# Placa3.net
KiCad netlist of a schematic drawn in Altium Designer
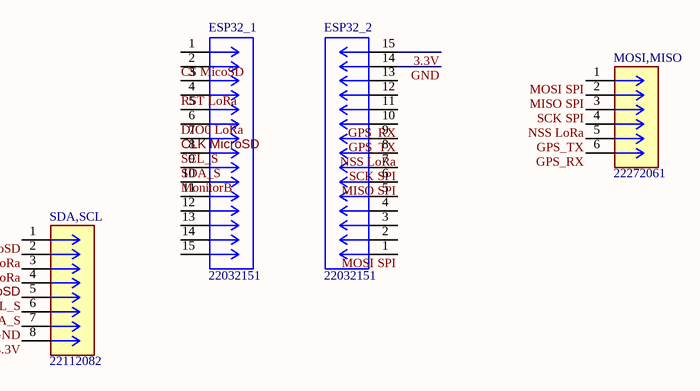
[diagram p0: Placa3.SchDoc]

(export (version "E")
  (design (tool "Eeschema 10.0.6"))
  (components
    (comp (ref "ESP32_1")
      (value "22032151")
      (footprint "CONN15X1_22032151_MOL")
      (description "Conn Unshrouded Header HDR 15 POS 2.54mm Solder ST Thru-Hole KKÂ® Bag")
      (fields (field (name "MF") "Molex"))
      (libsource (lib "22032151") (part "22032151"))
    )
    (comp (ref "ESP32_2")
      (value "22032151")
      (footprint "CONN15X1_22032151_MOL")
      (description "Conn Unshrouded Header HDR 15 POS 2.54mm Solder ST Thru-Hole KKÂ® Bag")
      (fields (field (name "MF") "Molex"))
      (libsource (lib "22032151") (part "22032151"))
    )
    (comp (ref "MOSI,MISO")
      (value "22272061")
      (footprint "CONN_AE-6410-06A_MOL")
      (libsource (lib "22272061") (part "22272061"))
    )
    (comp (ref "SDA,SCL")
      (value "22112082")
      (footprint "CONN_A-6373-08A_MOL")
      (description "KKÂ® 254 Solid Header, Vertical, with Friction Lock, 8 Circuits, Gold (Au) Plating")
      (fields (field (name "MF") "Molex") (field (name "MP") "22-11-2082"))
      (libsource (lib "22112082") (part "22112082"))
    )
  )
  (nets
    (net (code "1") (name "/3.3V") (class "Default")
      (node (ref "ESP32_2") (pin "15") (pinfunction "15_15") (pintype "passive"))
      (node (ref "SDA,SCL") (pin "8") (pinfunction "8_8") (pintype "passive"))
    )
    (net (code "2") (name "/CLK MicroSD") (class "Default")
      (node (ref "ESP32_1") (pin "8") (pinfunction "8_8") (pintype "passive"))
      (node (ref "SDA,SCL") (pin "4") (pinfunction "4_4") (pintype "passive"))
    )
    (net (code "3") (name "/CS MicoSD") (class "Default")
      (node (ref "ESP32_1") (pin "3") (pinfunction "3_3") (pintype "passive"))
      (node (ref "SDA,SCL") (pin "1") (pinfunction "1_1") (pintype "passive"))
    )
    (net (code "4") (name "/DIO0 LoRa") (class "Default")
      (node (ref "ESP32_1") (pin "7") (pinfunction "7_7") (pintype "passive"))
      (node (ref "SDA,SCL") (pin "3") (pinfunction "3_3") (pintype "passive"))
    )
    (net (code "5") (name "/GND") (class "Default")
      (node (ref "ESP32_2") (pin "14") (pinfunction "14_14") (pintype "passive"))
      (node (ref "SDA,SCL") (pin "7") (pinfunction "7_7") (pintype "passive"))
    )
    (net (code "6") (name "/GPS_RX") (class "Default")
      (node (ref "ESP32_2") (pin "10") (pinfunction "10_10") (pintype "passive"))
      (node (ref "MOSI,MISO") (pin "6") (pinfunction "6_6") (pintype "passive"))
    )
    (net (code "7") (name "/GPS_TX") (class "Default")
      (node (ref "ESP32_2") (pin "9") (pinfunction "9_9") (pintype "passive"))
      (node (ref "MOSI,MISO") (pin "5") (pinfunction "5_5") (pintype "passive"))
    )
    (net (code "8") (name "/MISO SPI") (class "Default")
      (node (ref "ESP32_2") (pin "6") (pinfunction "6_6") (pintype "passive"))
      (node (ref "MOSI,MISO") (pin "2") (pinfunction "2_2") (pintype "passive"))
    )
    (net (code "9") (name "/MOSI SPI") (class "Default")
      (node (ref "ESP32_2") (pin "1") (pinfunction "1_1") (pintype "passive"))
      (node (ref "MOSI,MISO") (pin "1") (pinfunction "1_1") (pintype "passive"))
    )
    (net (code "10") (name "/MonitorB") (class "Default")
      (node (ref "ESP32_1") (pin "11") (pinfunction "11_11") (pintype "passive"))
    )
    (net (code "11") (name "/NSS LoRa") (class "Default")
      (node (ref "ESP32_2") (pin "8") (pinfunction "8_8") (pintype "passive"))
      (node (ref "MOSI,MISO") (pin "4") (pinfunction "4_4") (pintype "passive"))
    )
    (net (code "12") (name "/RST LoRa") (class "Default")
      (node (ref "ESP32_1") (pin "5") (pinfunction "5_5") (pintype "passive"))
      (node (ref "SDA,SCL") (pin "2") (pinfunction "2_2") (pintype "passive"))
    )
    (net (code "13") (name "/SCK SPI") (class "Default")
      (node (ref "ESP32_2") (pin "7") (pinfunction "7_7") (pintype "passive"))
      (node (ref "MOSI,MISO") (pin "3") (pinfunction "3_3") (pintype "passive"))
    )
    (net (code "14") (name "/SCL_S") (class "Default")
      (node (ref "ESP32_1") (pin "9") (pinfunction "9_9") (pintype "passive"))
      (node (ref "SDA,SCL") (pin "5") (pinfunction "5_5") (pintype "passive"))
    )
    (net (code "15") (name "/SDA_S") (class "Default")
      (node (ref "ESP32_1") (pin "10") (pinfunction "10_10") (pintype "passive"))
      (node (ref "SDA,SCL") (pin "6") (pinfunction "6_6") (pintype "passive"))
    )
    (net (code "16") (name "unconnected-(ESP32_1-Pad1)") (class "Default")
      (node (ref "ESP32_1") (pin "1") (pinfunction "1_1") (pintype "passive"))
    )
    (net (code "17") (name "unconnected-(ESP32_1-Pad2)") (class "Default")
      (node (ref "ESP32_1") (pin "2") (pinfunction "2_2") (pintype "passive"))
    )
    (net (code "18") (name "unconnected-(ESP32_1-Pad4)") (class "Default")
      (node (ref "ESP32_1") (pin "4") (pinfunction "4_4") (pintype "passive"))
    )
    (net (code "19") (name "unconnected-(ESP32_1-Pad6)") (class "Default")
      (node (ref "ESP32_1") (pin "6") (pinfunction "6_6") (pintype "passive"))
    )
    (net (code "20") (name "unconnected-(ESP32_1-Pad12)") (class "Default")
      (node (ref "ESP32_1") (pin "12") (pinfunction "12_12") (pintype "passive"))
    )
    (net (code "21") (name "unconnected-(ESP32_1-Pad13)") (class "Default")
      (node (ref "ESP32_1") (pin "13") (pinfunction "13_13") (pintype "passive"))
    )
    (net (code "22") (name "unconnected-(ESP32_1-Pad14)") (class "Default")
      (node (ref "ESP32_1") (pin "14") (pinfunction "14_14") (pintype "passive"))
    )
    (net (code "23") (name "unconnected-(ESP32_1-Pad15)") (class "Default")
      (node (ref "ESP32_1") (pin "15") (pinfunction "15_15") (pintype "passive"))
    )
    (net (code "24") (name "unconnected-(ESP32_2-Pad2)") (class "Default")
      (node (ref "ESP32_2") (pin "2") (pinfunction "2_2") (pintype "passive"))
    )
    (net (code "25") (name "unconnected-(ESP32_2-Pad3)") (class "Default")
      (node (ref "ESP32_2") (pin "3") (pinfunction "3_3") (pintype "passive"))
    )
    (net (code "26") (name "unconnected-(ESP32_2-Pad4)") (class "Default")
      (node (ref "ESP32_2") (pin "4") (pinfunction "4_4") (pintype "passive"))
    )
    (net (code "27") (name "unconnected-(ESP32_2-Pad5)") (class "Default")
      (node (ref "ESP32_2") (pin "5") (pinfunction "5_5") (pintype "passive"))
    )
    (net (code "28") (name "unconnected-(ESP32_2-Pad11)") (class "Default")
      (node (ref "ESP32_2") (pin "11") (pinfunction "11_11") (pintype "passive"))
    )
    (net (code "29") (name "unconnected-(ESP32_2-Pad12)") (class "Default")
      (node (ref "ESP32_2") (pin "12") (pinfunction "12_12") (pintype "passive"))
    )
    (net (code "30") (name "unconnected-(ESP32_2-Pad13)") (class "Default")
      (node (ref "ESP32_2") (pin "13") (pinfunction "13_13") (pintype "passive"))
    )
  )
)
